# 4_STM32F334R8T6Board_FilterAndOutputs.net
KiCad netlist of a schematic drawn in Altium Designer
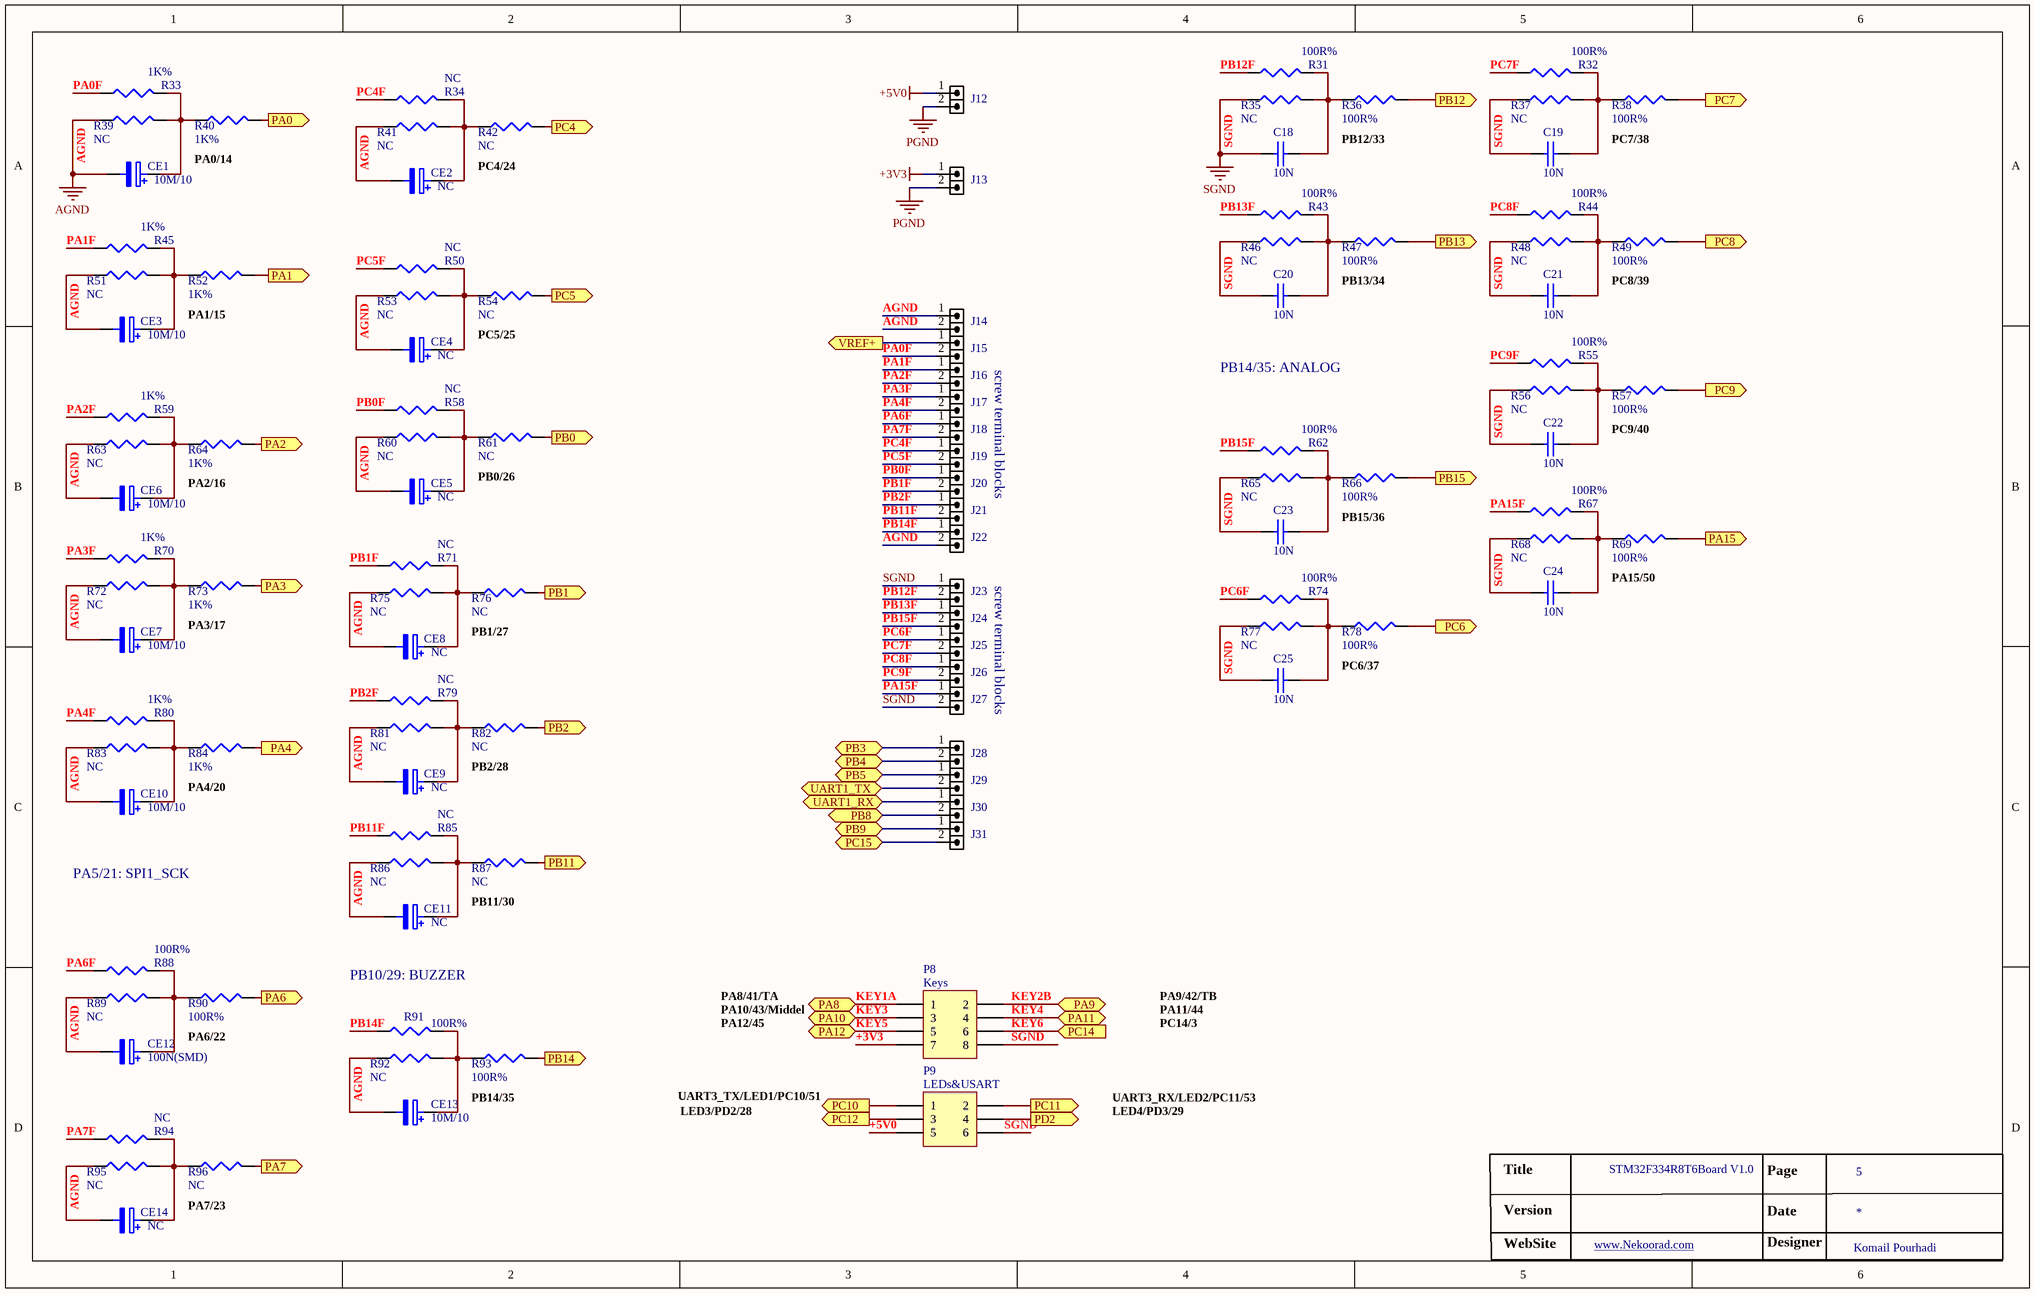
[diagram p0: [4]STM32F334R8T6Board_FilterAndOutputs.SchDoc]

(export (version "E")
  (design (tool "Eeschema 10.0.6"))
  (components
    (comp (ref "C18") (value "10N") (footprint "SMD_CAP_1206") (libsource (lib "*") (part "C")))
    (comp (ref "C19") (value "10N") (footprint "SMD_CAP_1206") (libsource (lib "*") (part "C")))
    (comp (ref "C20") (value "10N") (footprint "SMD_CAP_1206") (libsource (lib "*") (part "C")))
    (comp (ref "C21") (value "10N") (footprint "SMD_CAP_1206") (libsource (lib "*") (part "C")))
    (comp (ref "C22") (value "10N") (footprint "SMD_CAP_1206") (libsource (lib "*") (part "C")))
    (comp (ref "C23") (value "10N") (footprint "SMD_CAP_1206") (libsource (lib "*") (part "C")))
    (comp (ref "C24") (value "10N") (footprint "SMD_CAP_1206") (libsource (lib "*") (part "C")))
    (comp (ref "C25") (value "10N") (footprint "SMD_CAP_1206") (libsource (lib "*") (part "C")))
    (comp (ref "CE1") (value "10M/10") (footprint "SMD_ECAP_D") (libsource (lib "*") (part "E")))
    (comp (ref "CE2") (value "NC") (footprint "SMD_ECAP_D") (libsource (lib "*") (part "E")))
    (comp (ref "CE3") (value "10M/10") (footprint "SMD_ECAP_D") (libsource (lib "*") (part "E")))
    (comp (ref "CE4") (value "NC") (footprint "SMD_ECAP_D") (libsource (lib "*") (part "E")))
    (comp (ref "CE5") (value "NC") (footprint "SMD_ECAP_D") (libsource (lib "*") (part "E")))
    (comp (ref "CE6") (value "10M/10") (footprint "SMD_ECAP_D") (libsource (lib "*") (part "E")))
    (comp (ref "CE7") (value "10M/10") (footprint "SMD_ECAP_D") (libsource (lib "*") (part "E")))
    (comp (ref "CE8") (value "NC") (footprint "SMD_ECAP_D") (libsource (lib "*") (part "E")))
    (comp (ref "CE9") (value "NC") (footprint "SMD_ECAP_D") (libsource (lib "*") (part "E")))
    (comp (ref "CE10") (value "10M/10") (footprint "SMD_ECAP_D") (libsource (lib "*") (part "E")))
    (comp (ref "CE11") (value "NC") (footprint "SMD_ECAP_D") (libsource (lib "*") (part "E")))
    (comp (ref "CE12") (value "100N(SMD)") (footprint "SMD_ECAP_D") (libsource (lib "*") (part "E")))
    (comp (ref "CE13") (value "10M/10") (footprint "SMD_ECAP_D") (libsource (lib "*") (part "E")))
    (comp (ref "CE14") (value "NC") (footprint "SMD_ECAP_D") (libsource (lib "*") (part "E")))
    (comp (ref "J12")
      (value "HDRM2")
      (footprint "header screw 2*1")
      (description "CONN, HEADER, Male, pitch: 2.54mm, 2POS")
      (libsource (lib "conn_header") (part "HDR_M_1X2"))
    )
    (comp (ref "J13")
      (value "HDRM2")
      (footprint "header screw 2*1")
      (description "CONN, HEADER, Male, pitch: 2.54mm, 2POS")
      (libsource (lib "conn_header") (part "HDR_M_1X2"))
    )
    (comp (ref "J14")
      (value "HDRM2")
      (footprint "header screw 2*1")
      (description "CONN, HEADER, Male, pitch: 2.54mm, 2POS")
      (libsource (lib "conn_header") (part "HDR_M_1X2"))
    )
    (comp (ref "J15")
      (value "HDRM2")
      (footprint "header screw 2*1")
      (description "CONN, HEADER, Male, pitch: 2.54mm, 2POS")
      (libsource (lib "conn_header") (part "HDR_M_1X2"))
    )
    (comp (ref "J16")
      (value "HDRM2")
      (footprint "header screw 2*1")
      (description "CONN, HEADER, Male, pitch: 2.54mm, 2POS")
      (libsource (lib "conn_header") (part "HDR_M_1X2"))
    )
    (comp (ref "J17")
      (value "HDRM2")
      (footprint "header screw 2*1")
      (description "CONN, HEADER, Male, pitch: 2.54mm, 2POS")
      (libsource (lib "conn_header") (part "HDR_M_1X2"))
    )
    (comp (ref "J18")
      (value "HDRM2")
      (footprint "header screw 2*1")
      (description "CONN, HEADER, Male, pitch: 2.54mm, 2POS")
      (libsource (lib "conn_header") (part "HDR_M_1X2"))
    )
    (comp (ref "J19")
      (value "HDRM2")
      (footprint "header screw 2*1")
      (description "CONN, HEADER, Male, pitch: 2.54mm, 2POS")
      (libsource (lib "conn_header") (part "HDR_M_1X2"))
    )
    (comp (ref "J20")
      (value "HDRM2")
      (footprint "header screw 2*1")
      (description "CONN, HEADER, Male, pitch: 2.54mm, 2POS")
      (libsource (lib "conn_header") (part "HDR_M_1X2"))
    )
    (comp (ref "J21")
      (value "HDRM2")
      (footprint "header screw 2*1")
      (description "CONN, HEADER, Male, pitch: 2.54mm, 2POS")
      (libsource (lib "conn_header") (part "HDR_M_1X2"))
    )
    (comp (ref "J22")
      (value "HDRM2")
      (footprint "header screw 2*1")
      (description "CONN, HEADER, Male, pitch: 2.54mm, 2POS")
      (libsource (lib "conn_header") (part "HDR_M_1X2"))
    )
    (comp (ref "J23")
      (value "HDRM2")
      (footprint "header screw 2*1")
      (description "CONN, HEADER, Male, pitch: 2.54mm, 2POS")
      (libsource (lib "conn_header") (part "HDR_M_1X2"))
    )
    (comp (ref "J24")
      (value "HDRM2")
      (footprint "header screw 2*1")
      (description "CONN, HEADER, Male, pitch: 2.54mm, 2POS")
      (libsource (lib "conn_header") (part "HDR_M_1X2"))
    )
    (comp (ref "J25")
      (value "HDRM2")
      (footprint "header screw 2*1")
      (description "CONN, HEADER, Male, pitch: 2.54mm, 2POS")
      (libsource (lib "conn_header") (part "HDR_M_1X2"))
    )
    (comp (ref "J26")
      (value "HDRM2")
      (footprint "header screw 2*1")
      (description "CONN, HEADER, Male, pitch: 2.54mm, 2POS")
      (libsource (lib "conn_header") (part "HDR_M_1X2"))
    )
    (comp (ref "J27")
      (value "HDRM2")
      (footprint "header screw 2*1")
      (description "CONN, HEADER, Male, pitch: 2.54mm, 2POS")
      (libsource (lib "conn_header") (part "HDR_M_1X2"))
    )
    (comp (ref "J28")
      (value "HDRM2")
      (footprint "header screw 2*1")
      (description "CONN, HEADER, Male, pitch: 2.54mm, 2POS")
      (libsource (lib "conn_header") (part "HDR_M_1X2"))
    )
    (comp (ref "J29")
      (value "HDRM2")
      (footprint "header screw 2*1")
      (description "CONN, HEADER, Male, pitch: 2.54mm, 2POS")
      (libsource (lib "conn_header") (part "HDR_M_1X2"))
    )
    (comp (ref "J30")
      (value "HDRM2")
      (footprint "header screw 2*1")
      (description "CONN, HEADER, Male, pitch: 2.54mm, 2POS")
      (libsource (lib "conn_header") (part "HDR_M_1X2"))
    )
    (comp (ref "J31")
      (value "HDRM2")
      (footprint "header screw 2*1")
      (description "CONN, HEADER, Male, pitch: 2.54mm, 2POS")
      (libsource (lib "conn_header") (part "HDR_M_1X2"))
    )
    (comp (ref "P8")
      (value "Keys")
      (footprint "IDC8-BOX")
      (description "Header, 4-Pin, Dual row")
      (fields (field (name "PUBLISHER") "Altium Limited"))
      (libsource (lib "Miscellaneous Connectors") (part "Header 4X2"))
    )
    (comp (ref "P9")
      (value "LEDs&USART")
      (footprint "IDC6-BOX")
      (description "Header, 3-Pin, Dual row")
      (fields (field (name "PUBLISHER") "Altium Limited"))
      (libsource (lib "Miscellaneous Connectors") (part "Header 3X2"))
    )
    (comp (ref "R31") (value "100R%") (footprint "RES_1206") (libsource (lib "*") (part "R")))
    (comp (ref "R32") (value "100R%") (footprint "RES_1206") (libsource (lib "*") (part "R")))
    (comp (ref "R33") (value "1K%") (footprint "RES_1206") (libsource (lib "*") (part "R")))
    (comp (ref "R34") (value "NC") (footprint "RES_1206") (libsource (lib "*") (part "R")))
    (comp (ref "R35") (value "NC") (footprint "RES_1206") (libsource (lib "*") (part "R")))
    (comp (ref "R36") (value "100R%") (footprint "RES_1206") (libsource (lib "*") (part "R")))
    (comp (ref "R37") (value "NC") (footprint "RES_1206") (libsource (lib "*") (part "R")))
    (comp (ref "R38") (value "100R%") (footprint "RES_1206") (libsource (lib "*") (part "R")))
    (comp (ref "R39") (value "NC") (footprint "RES_1206") (libsource (lib "*") (part "R")))
    (comp (ref "R40") (value "1K%") (footprint "RES_1206") (libsource (lib "*") (part "R")))
    (comp (ref "R41") (value "NC") (footprint "RES_1206") (libsource (lib "*") (part "R")))
    (comp (ref "R42") (value "NC") (footprint "RES_1206") (libsource (lib "*") (part "R")))
    (comp (ref "R43") (value "100R%") (footprint "RES_1206") (libsource (lib "*") (part "R")))
    (comp (ref "R44") (value "100R%") (footprint "RES_1206") (libsource (lib "*") (part "R")))
    (comp (ref "R45") (value "1K%") (footprint "RES_1206") (libsource (lib "*") (part "R")))
    (comp (ref "R46") (value "NC") (footprint "RES_1206") (libsource (lib "*") (part "R")))
    (comp (ref "R47") (value "100R%") (footprint "RES_1206") (libsource (lib "*") (part "R")))
    (comp (ref "R48") (value "NC") (footprint "RES_1206") (libsource (lib "*") (part "R")))
    (comp (ref "R49") (value "100R%") (footprint "RES_1206") (libsource (lib "*") (part "R")))
    (comp (ref "R50") (value "NC") (footprint "RES_1206") (libsource (lib "*") (part "R")))
    (comp (ref "R51") (value "NC") (footprint "RES_1206") (libsource (lib "*") (part "R")))
    (comp (ref "R52") (value "1K%") (footprint "RES_1206") (libsource (lib "*") (part "R")))
    (comp (ref "R53") (value "NC") (footprint "RES_1206") (libsource (lib "*") (part "R")))
    (comp (ref "R54") (value "NC") (footprint "RES_1206") (libsource (lib "*") (part "R")))
    (comp (ref "R55") (value "100R%") (footprint "RES_1206") (libsource (lib "*") (part "R")))
    (comp (ref "R56") (value "NC") (footprint "RES_1206") (libsource (lib "*") (part "R")))
    (comp (ref "R57") (value "100R%") (footprint "RES_1206") (libsource (lib "*") (part "R")))
    (comp (ref "R58") (value "NC") (footprint "RES_1206") (libsource (lib "*") (part "R")))
    (comp (ref "R59") (value "1K%") (footprint "RES_1206") (libsource (lib "*") (part "R")))
    (comp (ref "R60") (value "NC") (footprint "RES_1206") (libsource (lib "*") (part "R")))
    (comp (ref "R61") (value "NC") (footprint "RES_1206") (libsource (lib "*") (part "R")))
    (comp (ref "R62") (value "100R%") (footprint "RES_1206") (libsource (lib "*") (part "R")))
    (comp (ref "R63") (value "NC") (footprint "RES_1206") (libsource (lib "*") (part "R")))
    (comp (ref "R64") (value "1K%") (footprint "RES_1206") (libsource (lib "*") (part "R")))
    (comp (ref "R65") (value "NC") (footprint "RES_1206") (libsource (lib "*") (part "R")))
    (comp (ref "R66") (value "100R%") (footprint "RES_1206") (libsource (lib "*") (part "R")))
    (comp (ref "R67") (value "100R%") (footprint "RES_1206") (libsource (lib "*") (part "R")))
    (comp (ref "R68") (value "NC") (footprint "RES_1206") (libsource (lib "*") (part "R")))
    (comp (ref "R69") (value "100R%") (footprint "RES_1206") (libsource (lib "*") (part "R")))
    (comp (ref "R70") (value "1K%") (footprint "RES_1206") (libsource (lib "*") (part "R")))
    (comp (ref "R71") (value "NC") (footprint "RES_1206") (libsource (lib "*") (part "R")))
    (comp (ref "R72") (value "NC") (footprint "RES_1206") (libsource (lib "*") (part "R")))
    (comp (ref "R73") (value "1K%") (footprint "RES_1206") (libsource (lib "*") (part "R")))
    (comp (ref "R74") (value "100R%") (footprint "RES_1206") (libsource (lib "*") (part "R")))
    (comp (ref "R75") (value "NC") (footprint "RES_1206") (libsource (lib "*") (part "R")))
    (comp (ref "R76") (value "NC") (footprint "RES_1206") (libsource (lib "*") (part "R")))
    (comp (ref "R77") (value "NC") (footprint "RES_1206") (libsource (lib "*") (part "R")))
    (comp (ref "R78") (value "100R%") (footprint "RES_1206") (libsource (lib "*") (part "R")))
    (comp (ref "R79") (value "NC") (footprint "RES_1206") (libsource (lib "*") (part "R")))
    (comp (ref "R80") (value "1K%") (footprint "RES_1206") (libsource (lib "*") (part "R")))
    (comp (ref "R81") (value "NC") (footprint "RES_1206") (libsource (lib "*") (part "R")))
    (comp (ref "R82") (value "NC") (footprint "RES_1206") (libsource (lib "*") (part "R")))
    (comp (ref "R83") (value "NC") (footprint "RES_1206") (libsource (lib "*") (part "R")))
    (comp (ref "R84") (value "1K%") (footprint "RES_1206") (libsource (lib "*") (part "R")))
    (comp (ref "R85") (value "NC") (footprint "RES_1206") (libsource (lib "*") (part "R")))
    (comp (ref "R86") (value "NC") (footprint "RES_1206") (libsource (lib "*") (part "R")))
    (comp (ref "R87") (value "NC") (footprint "RES_1206") (libsource (lib "*") (part "R")))
    (comp (ref "R88") (value "100R%") (footprint "RES_1206") (libsource (lib "*") (part "R")))
    (comp (ref "R89") (value "NC") (footprint "RES_1206") (libsource (lib "*") (part "R")))
    (comp (ref "R90") (value "100R%") (footprint "RES_1206") (libsource (lib "*") (part "R")))
    (comp (ref "R91") (value "100R%") (footprint "RES_1206") (libsource (lib "*") (part "R")))
    (comp (ref "R92") (value "NC") (footprint "RES_1206") (libsource (lib "*") (part "R")))
    (comp (ref "R93") (value "100R%") (footprint "RES_1206") (libsource (lib "*") (part "R")))
    (comp (ref "R94") (value "NC") (footprint "RES_1206") (libsource (lib "*") (part "R")))
    (comp (ref "R95") (value "NC") (footprint "RES_1206") (libsource (lib "*") (part "R")))
    (comp (ref "R96") (value "NC") (footprint "RES_1206") (libsource (lib "*") (part "R")))
  )
  (nets
    (net (code "1") (name "+3V3") (class "Default")
      (node (ref "J13") (pin "1") (pinfunction "1_1") (pintype "passive"))
      (node (ref "P8") (pin "7") (pinfunction "7_7") (pintype "passive"))
    )
    (net (code "2") (name "+5V0") (class "Default")
      (node (ref "J12") (pin "1") (pinfunction "1_1") (pintype "passive"))
      (node (ref "P9") (pin "5") (pinfunction "5_5") (pintype "passive"))
    )
    (net (code "3") (name "/KEY1A") (class "Default")
      (node (ref "P8") (pin "1") (pinfunction "1_1") (pintype "passive"))
    )
    (net (code "4") (name "/KEY2B") (class "Default")
      (node (ref "P8") (pin "2") (pinfunction "2_2") (pintype "passive"))
    )
    (net (code "5") (name "/KEY3") (class "Default")
      (node (ref "P8") (pin "3") (pinfunction "3_3") (pintype "passive"))
    )
    (net (code "6") (name "/KEY4") (class "Default")
      (node (ref "P8") (pin "4") (pinfunction "4_4") (pintype "passive"))
    )
    (net (code "7") (name "/KEY5") (class "Default")
      (node (ref "P8") (pin "5") (pinfunction "5_5") (pintype "passive"))
    )
    (net (code "8") (name "/KEY6") (class "Default")
      (node (ref "P8") (pin "6") (pinfunction "6_6") (pintype "passive"))
    )
    (net (code "9") (name "/PA0") (class "Default") (node (ref "R40") (pin "2") (pintype "passive")))
    (net (code "10") (name "/PA0F") (class "Default")
      (node (ref "J15") (pin "2") (pinfunction "2_2") (pintype "passive"))
      (node (ref "R33") (pin "1") (pintype "passive"))
    )
    (net (code "11") (name "/PA1") (class "Default") (node (ref "R52") (pin "2") (pintype "passive")))
    (net (code "12") (name "/PA1F") (class "Default")
      (node (ref "J16") (pin "1") (pinfunction "1_1") (pintype "passive"))
      (node (ref "R45") (pin "1") (pintype "passive"))
    )
    (net (code "13") (name "/PA2") (class "Default") (node (ref "R64") (pin "2") (pintype "passive")))
    (net (code "14") (name "/PA2F") (class "Default")
      (node (ref "J16") (pin "2") (pinfunction "2_2") (pintype "passive"))
      (node (ref "R59") (pin "1") (pintype "passive"))
    )
    (net (code "15") (name "/PA3") (class "Default") (node (ref "R73") (pin "2") (pintype "passive")))
    (net (code "16") (name "/PA3F") (class "Default")
      (node (ref "J17") (pin "1") (pinfunction "1_1") (pintype "passive"))
      (node (ref "R70") (pin "1") (pintype "passive"))
    )
    (net (code "17") (name "/PA4") (class "Default") (node (ref "R84") (pin "2") (pintype "passive")))
    (net (code "18") (name "/PA4F") (class "Default")
      (node (ref "J17") (pin "2") (pinfunction "2_2") (pintype "passive"))
      (node (ref "R80") (pin "1") (pintype "passive"))
    )
    (net (code "19") (name "/PA6") (class "Default") (node (ref "R90") (pin "2") (pintype "passive")))
    (net (code "20") (name "/PA6F") (class "Default")
      (node (ref "J18") (pin "1") (pinfunction "1_1") (pintype "passive"))
      (node (ref "R88") (pin "1") (pintype "passive"))
    )
    (net (code "21") (name "/PA7") (class "Default") (node (ref "R96") (pin "2") (pintype "passive")))
    (net (code "22") (name "/PA7F") (class "Default")
      (node (ref "J18") (pin "2") (pinfunction "2_2") (pintype "passive"))
      (node (ref "R94") (pin "1") (pintype "passive"))
    )
    (net (code "23") (name "/PA15") (class "Default") (node (ref "R69") (pin "2") (pintype "passive")))
    (net (code "24") (name "/PA15F") (class "Default")
      (node (ref "J27") (pin "1") (pinfunction "1_1") (pintype "passive"))
      (node (ref "R67") (pin "1") (pintype "passive"))
    )
    (net (code "25") (name "/PB0") (class "Default") (node (ref "R61") (pin "2") (pintype "passive")))
    (net (code "26") (name "/PB0F") (class "Default")
      (node (ref "J20") (pin "1") (pinfunction "1_1") (pintype "passive"))
      (node (ref "R58") (pin "1") (pintype "passive"))
    )
    (net (code "27") (name "/PB1") (class "Default") (node (ref "R76") (pin "2") (pintype "passive")))
    (net (code "28") (name "/PB1F") (class "Default")
      (node (ref "J20") (pin "2") (pinfunction "2_2") (pintype "passive"))
      (node (ref "R71") (pin "1") (pintype "passive"))
    )
    (net (code "29") (name "/PB2") (class "Default") (node (ref "R82") (pin "2") (pintype "passive")))
    (net (code "30") (name "/PB2F") (class "Default")
      (node (ref "J21") (pin "1") (pinfunction "1_1") (pintype "passive"))
      (node (ref "R79") (pin "1") (pintype "passive"))
    )
    (net (code "31") (name "/PB3") (class "Default")
      (node (ref "J28") (pin "1") (pinfunction "1_1") (pintype "passive"))
    )
    (net (code "32") (name "/PB4") (class "Default")
      (node (ref "J28") (pin "2") (pinfunction "2_2") (pintype "passive"))
    )
    (net (code "33") (name "/PB5") (class "Default")
      (node (ref "J29") (pin "1") (pinfunction "1_1") (pintype "passive"))
    )
    (net (code "34") (name "/PB8") (class "Default")
      (node (ref "J30") (pin "2") (pinfunction "2_2") (pintype "passive"))
    )
    (net (code "35") (name "/PB9") (class "Default")
      (node (ref "J31") (pin "1") (pinfunction "1_1") (pintype "passive"))
    )
    (net (code "36") (name "/PB11") (class "Default") (node (ref "R87") (pin "2") (pintype "passive")))
    (net (code "37") (name "/PB11F") (class "Default")
      (node (ref "J21") (pin "2") (pinfunction "2_2") (pintype "passive"))
      (node (ref "R85") (pin "1") (pintype "passive"))
    )
    (net (code "38") (name "/PB12") (class "Default") (node (ref "R36") (pin "2") (pintype "passive")))
    (net (code "39") (name "/PB12F") (class "Default")
      (node (ref "J23") (pin "2") (pinfunction "2_2") (pintype "passive"))
      (node (ref "R31") (pin "1") (pintype "passive"))
    )
    (net (code "40") (name "/PB13") (class "Default") (node (ref "R47") (pin "2") (pintype "passive")))
    (net (code "41") (name "/PB13F") (class "Default")
      (node (ref "J24") (pin "1") (pinfunction "1_1") (pintype "passive"))
      (node (ref "R43") (pin "1") (pintype "passive"))
    )
    (net (code "42") (name "/PB14") (class "Default") (node (ref "R93") (pin "2") (pintype "passive")))
    (net (code "43") (name "/PB14F") (class "Default")
      (node (ref "J22") (pin "1") (pinfunction "1_1") (pintype "passive"))
      (node (ref "R91") (pin "1") (pintype "passive"))
    )
    (net (code "44") (name "/PB15") (class "Default") (node (ref "R66") (pin "2") (pintype "passive")))
    (net (code "45") (name "/PB15F") (class "Default")
      (node (ref "J24") (pin "2") (pinfunction "2_2") (pintype "passive"))
      (node (ref "R62") (pin "1") (pintype "passive"))
    )
    (net (code "46") (name "/PC4") (class "Default") (node (ref "R42") (pin "2") (pintype "passive")))
    (net (code "47") (name "/PC4F") (class "Default")
      (node (ref "J19") (pin "1") (pinfunction "1_1") (pintype "passive"))
      (node (ref "R34") (pin "1") (pintype "passive"))
    )
    (net (code "48") (name "/PC5") (class "Default") (node (ref "R54") (pin "2") (pintype "passive")))
    (net (code "49") (name "/PC5F") (class "Default")
      (node (ref "J19") (pin "2") (pinfunction "2_2") (pintype "passive"))
      (node (ref "R50") (pin "1") (pintype "passive"))
    )
    (net (code "50") (name "/PC6") (class "Default") (node (ref "R78") (pin "2") (pintype "passive")))
    (net (code "51") (name "/PC6F") (class "Default")
      (node (ref "J25") (pin "1") (pinfunction "1_1") (pintype "passive"))
      (node (ref "R74") (pin "1") (pintype "passive"))
    )
    (net (code "52") (name "/PC7") (class "Default") (node (ref "R38") (pin "2") (pintype "passive")))
    (net (code "53") (name "/PC7F") (class "Default")
      (node (ref "J25") (pin "2") (pinfunction "2_2") (pintype "passive"))
      (node (ref "R32") (pin "1") (pintype "passive"))
    )
    (net (code "54") (name "/PC8") (class "Default") (node (ref "R49") (pin "2") (pintype "passive")))
    (net (code "55") (name "/PC8F") (class "Default")
      (node (ref "J26") (pin "1") (pinfunction "1_1") (pintype "passive"))
      (node (ref "R44") (pin "1") (pintype "passive"))
    )
    (net (code "56") (name "/PC9") (class "Default") (node (ref "R57") (pin "2") (pintype "passive")))
    (net (code "57") (name "/PC9F") (class "Default")
      (node (ref "J26") (pin "2") (pinfunction "2_2") (pintype "passive"))
      (node (ref "R55") (pin "1") (pintype "passive"))
    )
    (net (code "58") (name "/PC10") (class "Default")
      (node (ref "P9") (pin "1") (pinfunction "1_1") (pintype "passive"))
    )
    (net (code "59") (name "/PC11") (class "Default")
      (node (ref "P9") (pin "2") (pinfunction "2_2") (pintype "passive"))
    )
    (net (code "60") (name "/PC12") (class "Default")
      (node (ref "P9") (pin "3") (pinfunction "3_3") (pintype "passive"))
    )
    (net (code "61") (name "/PC15") (class "Default")
      (node (ref "J31") (pin "2") (pinfunction "2_2") (pintype "passive"))
    )
    (net (code "62") (name "/PD2") (class "Default")
      (node (ref "P9") (pin "4") (pinfunction "4_4") (pintype "passive"))
    )
    (net (code "63") (name "/UART1_RX") (class "Default")
      (node (ref "J30") (pin "1") (pinfunction "1_1") (pintype "passive"))
    )
    (net (code "65") (name "/VREF+") (class "Default")
      (node (ref "J15") (pin "1") (pinfunction "1_1") (pintype "passive"))
    )
    (net (code "66") (name "AGND") (class "Default")
      (node (ref "CE1") (pin "2") (pintype "passive"))
      (node (ref "CE10") (pin "2") (pintype "passive"))
      (node (ref "CE11") (pin "2") (pintype "passive"))
      (node (ref "CE12") (pin "2") (pintype "passive"))
      (node (ref "CE13") (pin "2") (pintype "passive"))
      (node (ref "CE14") (pin "2") (pintype "passive"))
      (node (ref "CE2") (pin "2") (pintype "passive"))
      (node (ref "CE3") (pin "2") (pintype "passive"))
      (node (ref "CE4") (pin "2") (pintype "passive"))
      (node (ref "CE5") (pin "2") (pintype "passive"))
      (node (ref "CE6") (pin "2") (pintype "passive"))
      (node (ref "CE7") (pin "2") (pintype "passive"))
      (node (ref "CE8") (pin "2") (pintype "passive"))
      (node (ref "CE9") (pin "2") (pintype "passive"))
      (node (ref "J14") (pin "1") (pinfunction "1_1") (pintype "passive"))
      (node (ref "J14") (pin "2") (pinfunction "2_2") (pintype "passive"))
      (node (ref "J22") (pin "2") (pinfunction "2_2") (pintype "passive"))
      (node (ref "R39") (pin "1") (pintype "passive"))
      (node (ref "R41") (pin "1") (pintype "passive"))
      (node (ref "R51") (pin "1") (pintype "passive"))
      (node (ref "R53") (pin "1") (pintype "passive"))
      (node (ref "R60") (pin "1") (pintype "passive"))
      (node (ref "R63") (pin "1") (pintype "passive"))
      (node (ref "R72") (pin "1") (pintype "passive"))
      (node (ref "R75") (pin "1") (pintype "passive"))
      (node (ref "R81") (pin "1") (pintype "passive"))
      (node (ref "R83") (pin "1") (pintype "passive"))
      (node (ref "R86") (pin "1") (pintype "passive"))
      (node (ref "R89") (pin "1") (pintype "passive"))
      (node (ref "R92") (pin "1") (pintype "passive"))
      (node (ref "R95") (pin "1") (pintype "passive"))
    )
    (net (code "67") (name "Net-(C18-Pad1)") (class "Default")
      (node (ref "C18") (pin "1") (pintype "passive"))
      (node (ref "R31") (pin "2") (pintype "passive"))
      (node (ref "R35") (pin "2") (pintype "passive"))
      (node (ref "R36") (pin "1") (pintype "passive"))
    )
    (net (code "68") (name "Net-(C19-Pad1)") (class "Default")
      (node (ref "C19") (pin "1") (pintype "passive"))
      (node (ref "R32") (pin "2") (pintype "passive"))
      (node (ref "R37") (pin "2") (pintype "passive"))
      (node (ref "R38") (pin "1") (pintype "passive"))
    )
    (net (code "69") (name "Net-(C20-Pad1)") (class "Default")
      (node (ref "C20") (pin "1") (pintype "passive"))
      (node (ref "R43") (pin "2") (pintype "passive"))
      (node (ref "R46") (pin "2") (pintype "passive"))
      (node (ref "R47") (pin "1") (pintype "passive"))
    )
    (net (code "70") (name "Net-(C21-Pad1)") (class "Default")
      (node (ref "C21") (pin "1") (pintype "passive"))
      (node (ref "R44") (pin "2") (pintype "passive"))
      (node (ref "R48") (pin "2") (pintype "passive"))
      (node (ref "R49") (pin "1") (pintype "passive"))
    )
    (net (code "71") (name "Net-(C22-Pad1)") (class "Default")
      (node (ref "C22") (pin "1") (pintype "passive"))
      (node (ref "R55") (pin "2") (pintype "passive"))
      (node (ref "R56") (pin "2") (pintype "passive"))
      (node (ref "R57") (pin "1") (pintype "passive"))
    )
    (net (code "72") (name "Net-(C23-Pad1)") (class "Default")
      (node (ref "C23") (pin "1") (pintype "passive"))
      (node (ref "R62") (pin "2") (pintype "passive"))
      (node (ref "R65") (pin "2") (pintype "passive"))
      (node (ref "R66") (pin "1") (pintype "passive"))
    )
    (net (code "73") (name "Net-(C24-Pad1)") (class "Default")
      (node (ref "C24") (pin "1") (pintype "passive"))
      (node (ref "R67") (pin "2") (pintype "passive"))
      (node (ref "R68") (pin "2") (pintype "passive"))
      (node (ref "R69") (pin "1") (pintype "passive"))
    )
    (net (code "74") (name "Net-(C25-Pad1)") (class "Default")
      (node (ref "C25") (pin "1") (pintype "passive"))
      (node (ref "R74") (pin "2") (pintype "passive"))
      (node (ref "R77") (pin "2") (pintype "passive"))
      (node (ref "R78") (pin "1") (pintype "passive"))
    )
    (net (code "75") (name "Net-(CE1-Pad1)") (class "Default")
      (node (ref "CE1") (pin "1") (pintype "passive"))
      (node (ref "R33") (pin "2") (pintype "passive"))
      (node (ref "R39") (pin "2") (pintype "passive"))
      (node (ref "R40") (pin "1") (pintype "passive"))
    )
    (net (code "76") (name "Net-(CE2-Pad1)") (class "Default")
      (node (ref "CE2") (pin "1") (pintype "passive"))
      (node (ref "R34") (pin "2") (pintype "passive"))
      (node (ref "R41") (pin "2") (pintype "passive"))
      (node (ref "R42") (pin "1") (pintype "passive"))
    )
    (net (code "77") (name "Net-(CE3-Pad1)") (class "Default")
      (node (ref "CE3") (pin "1") (pintype "passive"))
      (node (ref "R45") (pin "2") (pintype "passive"))
      (node (ref "R51") (pin "2") (pintype "passive"))
      (node (ref "R52") (pin "1") (pintype "passive"))
    )
    (net (code "78") (name "Net-(CE4-Pad1)") (class "Default")
      (node (ref "CE4") (pin "1") (pintype "passive"))
      (node (ref "R50") (pin "2") (pintype "passive"))
      (node (ref "R53") (pin "2") (pintype "passive"))
      (node (ref "R54") (pin "1") (pintype "passive"))
    )
    (net (code "79") (name "Net-(CE5-Pad1)") (class "Default")
      (node (ref "CE5") (pin "1") (pintype "passive"))
      (node (ref "R58") (pin "2") (pintype "passive"))
      (node (ref "R60") (pin "2") (pintype "passive"))
      (node (ref "R61") (pin "1") (pintype "passive"))
    )
    (net (code "80") (name "Net-(CE6-Pad1)") (class "Default")
      (node (ref "CE6") (pin "1") (pintype "passive"))
      (node (ref "R59") (pin "2") (pintype "passive"))
      (node (ref "R63") (pin "2") (pintype "passive"))
      (node (ref "R64") (pin "1") (pintype "passive"))
    )
    (net (code "81") (name "Net-(CE7-Pad1)") (class "Default")
      (node (ref "CE7") (pin "1") (pintype "passive"))
      (node (ref "R70") (pin "2") (pintype "passive"))
      (node (ref "R72") (pin "2") (pintype "passive"))
      (node (ref "R73") (pin "1") (pintype "passive"))
    )
    (net (code "82") (name "Net-(CE8-Pad1)") (class "Default")
      (node (ref "CE8") (pin "1") (pintype "passive"))
      (node (ref "R71") (pin "2") (pintype "passive"))
      (node (ref "R75") (pin "2") (pintype "passive"))
      (node (ref "R76") (pin "1") (pintype "passive"))
    )
    (net (code "83") (name "Net-(CE9-Pad1)") (class "Default")
      (node (ref "CE9") (pin "1") (pintype "passive"))
      (node (ref "R79") (pin "2") (pintype "passive"))
      (node (ref "R81") (pin "2") (pintype "passive"))
      (node (ref "R82") (pin "1") (pintype "passive"))
    )
    (net (code "84") (name "Net-(CE10-Pad1)") (class "Default")
      (node (ref "CE10") (pin "1") (pintype "passive"))
      (node (ref "R80") (pin "2") (pintype "passive"))
      (node (ref "R83") (pin "2") (pintype "passive"))
      (node (ref "R84") (pin "1") (pintype "passive"))
    )
    (net (code "85") (name "Net-(CE11-Pad1)") (class "Default")
      (node (ref "CE11") (pin "1") (pintype "passive"))
      (node (ref "R85") (pin "2") (pintype "passive"))
      (node (ref "R86") (pin "2") (pintype "passive"))
      (node (ref "R87") (pin "1") (pintype "passive"))
    )
    (net (code "86") (name "Net-(CE12-Pad1)") (class "Default")
      (node (ref "CE12") (pin "1") (pintype "passive"))
      (node (ref "R88") (pin "2") (pintype "passive"))
      (node (ref "R89") (pin "2") (pintype "passive"))
      (node (ref "R90") (pin "1") (pintype "passive"))
    )
    (net (code "87") (name "Net-(CE13-Pad1)") (class "Default")
      (node (ref "CE13") (pin "1") (pintype "passive"))
      (node (ref "R91") (pin "2") (pintype "passive"))
      (node (ref "R92") (pin "2") (pintype "passive"))
      (node (ref "R93") (pin "1") (pintype "passive"))
    )
    (net (code "88") (name "Net-(CE14-Pad1)") (class "Default")
      (node (ref "CE14") (pin "1") (pintype "passive"))
      (node (ref "R94") (pin "2") (pintype "passive"))
      (node (ref "R95") (pin "2") (pintype "passive"))
      (node (ref "R96") (pin "1") (pintype "passive"))
    )
    (net (code "89") (name "PGND") (class "Default")
      (node (ref "J12") (pin "2") (pinfunction "2_2") (pintype "passive"))
      (node (ref "J13") (pin "2") (pinfunction "2_2") (pintype "passive"))
    )
    (net (code "90") (name "SGND") (class "Default")
      (node (ref "C18") (pin "2") (pintype "passive"))
      (node (ref "C19") (pin "2") (pintype "passive"))
      (node (ref "C20") (pin "2") (pintype "passive"))
      (node (ref "C21") (pin "2") (pintype "passive"))
      (node (ref "C22") (pin "2") (pintype "passive"))
      (node (ref "C23") (pin "2") (pintype "passive"))
      (node (ref "C24") (pin "2") (pintype "passive"))
      (node (ref "C25") (pin "2") (pintype "passive"))
      (node (ref "J23") (pin "1") (pinfunction "1_1") (pintype "passive"))
      (node (ref "J27") (pin "2") (pinfunction "2_2") (pintype "passive"))
      (node (ref "P8") (pin "8") (pinfunction "8_8") (pintype "passive"))
      (node (ref "P9") (pin "6") (pinfunction "6_6") (pintype "passive"))
      (node (ref "R35") (pin "1") (pintype "passive"))
      (node (ref "R37") (pin "1") (pintype "passive"))
      (node (ref "R46") (pin "1") (pintype "passive"))
      (node (ref "R48") (pin "1") (pintype "passive"))
      (node (ref "R56") (pin "1") (pintype "passive"))
      (node (ref "R65") (pin "1") (pintype "passive"))
      (node (ref "R68") (pin "1") (pintype "passive"))
      (node (ref "R77") (pin "1") (pintype "passive"))
    )
    (net (code "91") (name "unconnected-(J29-Pad2)") (class "Default")
      (node (ref "J29") (pin "2") (pinfunction "2_2") (pintype "passive"))
    )
  )
)
